# Interconnect_board_v1p5.net
KiCad netlist of a schematic drawn in EAGLE
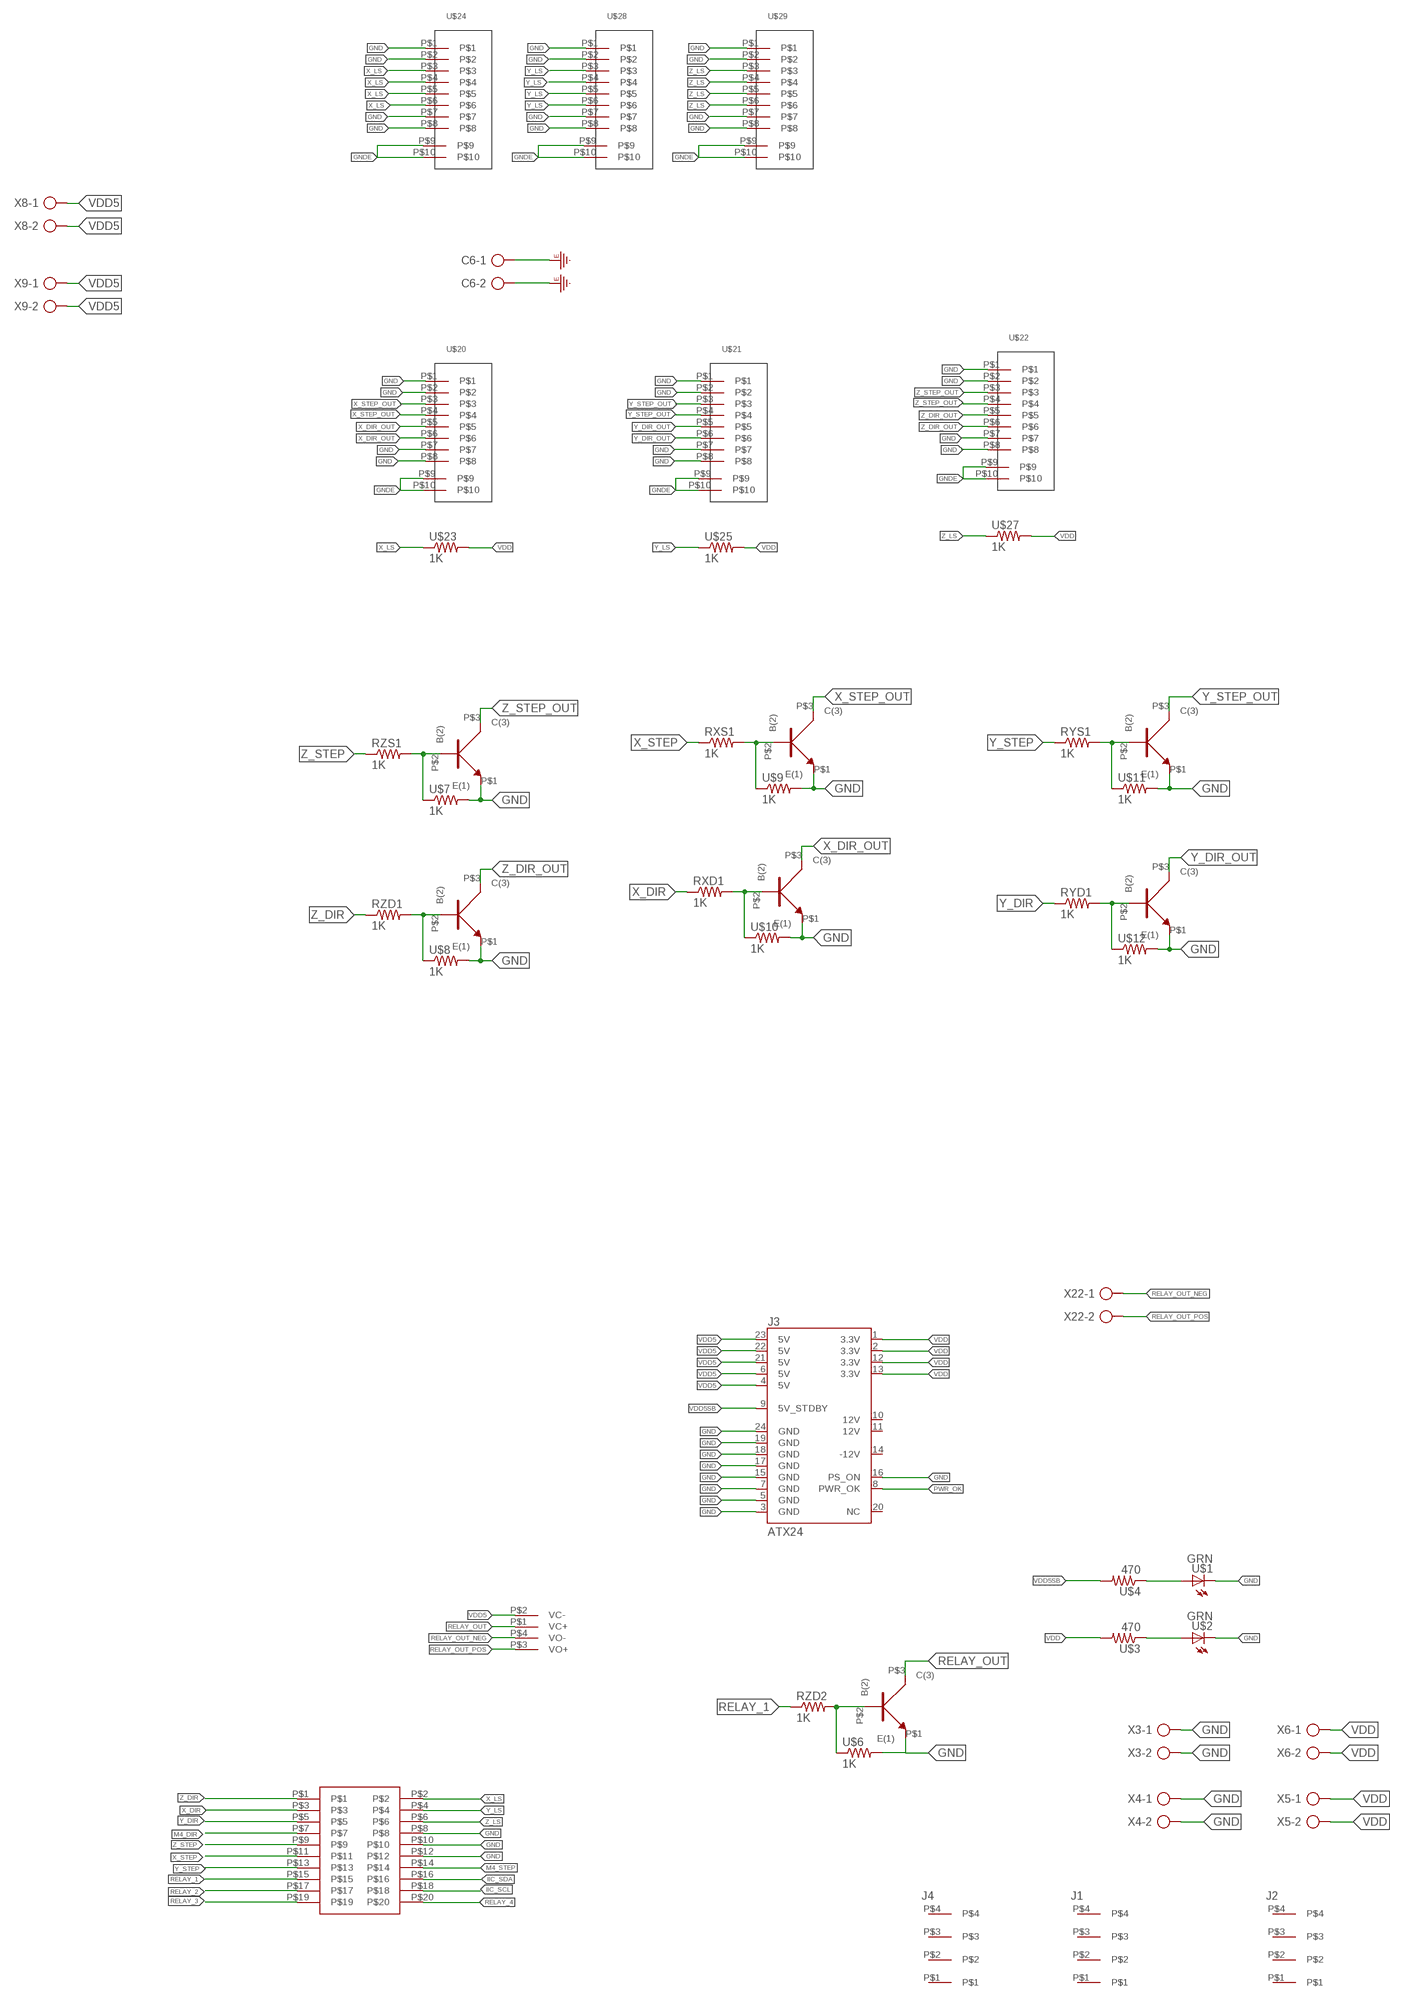
[diagram p0: schematic, sheet 1]

(export (version "E")
  (design (tool "Eeschema 10.0.6"))
  (components
    (comp (ref "C6")
      (value "AK300/2")
      (footprint "eagle-import:AK300_2")
      (libsource (lib "eagle-import") (part "AK300/2"))
    )
    (comp (ref "J1")
      (value "3.81MM_1_X_4_RT_ANGLE_PLUG_HEADER")
      (footprint "eagle-import:1X4_3.81MM_PITCH")
      (libsource (lib "eagle-import") (part "3.81MM_1_X_4_RT_ANGLE_PLUG_HEADER"))
    )
    (comp (ref "J2")
      (value "3.81MM_1_X_4_RT_ANGLE_PLUG_HEADER")
      (footprint "eagle-import:1X4_3.81MM_PITCH")
      (libsource (lib "eagle-import") (part "3.81MM_1_X_4_RT_ANGLE_PLUG_HEADER"))
    )
    (comp (ref "J3")
      (value "ATX24")
      (footprint "eagle-import:ATX24_STRAIGHT")
      (libsource (lib "eagle-import") (part "ATX24"))
    )
    (comp (ref "J4")
      (value "3.81MM_1_X_4_RT_ANGLE_PLUG_HEADER")
      (footprint "eagle-import:1X4_3.81MM_PITCH")
      (libsource (lib "eagle-import") (part "3.81MM_1_X_4_RT_ANGLE_PLUG_HEADER"))
    )
    (comp (ref "RXD1")
      (value "R_0805_1K")
      (footprint "eagle-import:R_0805_1K")
      (libsource (lib "eagle-import") (part "R_0805_1K"))
    )
    (comp (ref "RXS1")
      (value "R_0805_1K")
      (footprint "eagle-import:R_0805_1K")
      (libsource (lib "eagle-import") (part "R_0805_1K"))
    )
    (comp (ref "RYD1")
      (value "R_0805_1K")
      (footprint "eagle-import:R_0805_1K")
      (libsource (lib "eagle-import") (part "R_0805_1K"))
    )
    (comp (ref "RYS1")
      (value "R_0805_1K")
      (footprint "eagle-import:R_0805_1K")
      (libsource (lib "eagle-import") (part "R_0805_1K"))
    )
    (comp (ref "RZD1")
      (value "R_0805_1K")
      (footprint "eagle-import:R_0805_1K")
      (libsource (lib "eagle-import") (part "R_0805_1K"))
    )
    (comp (ref "RZD2")
      (value "R_0805_1K")
      (footprint "eagle-import:R_0805_1K")
      (libsource (lib "eagle-import") (part "R_0805_1K"))
    )
    (comp (ref "RZS1")
      (value "R_0805_1K")
      (footprint "eagle-import:R_0805_1K")
      (libsource (lib "eagle-import") (part "R_0805_1K"))
    )
    (comp (ref "U$1")
      (value "LED_0805_GREEN")
      (footprint "eagle-import:LED_0805_GREEN")
      (libsource (lib "eagle-import") (part "LED_0805_GREEN"))
    )
    (comp (ref "U$2")
      (value "LED_0805_GREEN")
      (footprint "eagle-import:LED_0805_GREEN")
      (libsource (lib "eagle-import") (part "LED_0805_GREEN"))
    )
    (comp (ref "U$3")
      (value "R_0805_470")
      (footprint "eagle-import:R_0805_470")
      (libsource (lib "eagle-import") (part "R_0805_470"))
    )
    (comp (ref "U$4")
      (value "R_0805_470")
      (footprint "eagle-import:R_0805_470")
      (libsource (lib "eagle-import") (part "R_0805_470"))
    )
    (comp (ref "U$5")
      (value "RELAY_KYOTO_KF0604D")
      (footprint "eagle-import:RELAY_KYOTO_KF0604D")
      (libsource (lib "eagle-import") (part "RELAY_KYOTO_KF0604D"))
    )
    (comp (ref "U$6")
      (value "R_0805_1K")
      (footprint "eagle-import:R_0805_1K")
      (libsource (lib "eagle-import") (part "R_0805_1K"))
    )
    (comp (ref "U$7")
      (value "R_0805_1K")
      (footprint "eagle-import:R_0805_1K")
      (libsource (lib "eagle-import") (part "R_0805_1K"))
    )
    (comp (ref "U$8")
      (value "R_0805_1K")
      (footprint "eagle-import:R_0805_1K")
      (libsource (lib "eagle-import") (part "R_0805_1K"))
    )
    (comp (ref "U$9")
      (value "R_0805_1K")
      (footprint "eagle-import:R_0805_1K")
      (libsource (lib "eagle-import") (part "R_0805_1K"))
    )
    (comp (ref "U$10")
      (value "R_0805_1K")
      (footprint "eagle-import:R_0805_1K")
      (libsource (lib "eagle-import") (part "R_0805_1K"))
    )
    (comp (ref "U$11")
      (value "R_0805_1K")
      (footprint "eagle-import:R_0805_1K")
      (libsource (lib "eagle-import") (part "R_0805_1K"))
    )
    (comp (ref "U$12")
      (value "R_0805_1K")
      (footprint "eagle-import:R_0805_1K")
      (libsource (lib "eagle-import") (part "R_0805_1K"))
    )
    (comp (ref "U$13")
      (value "TRANS_NPN")
      (footprint "eagle-import:TO_92_STRAIGHT")
      (libsource (lib "eagle-import") (part "TRANS_NPN"))
    )
    (comp (ref "U$14")
      (value "TRANS_NPN")
      (footprint "eagle-import:TO_92_STRAIGHT")
      (libsource (lib "eagle-import") (part "TRANS_NPN"))
    )
    (comp (ref "U$15")
      (value "TRANS_NPN")
      (footprint "eagle-import:TO_92_STRAIGHT")
      (libsource (lib "eagle-import") (part "TRANS_NPN"))
    )
    (comp (ref "U$16")
      (value "TRANS_NPN")
      (footprint "eagle-import:TO_92_STRAIGHT")
      (libsource (lib "eagle-import") (part "TRANS_NPN"))
    )
    (comp (ref "U$17")
      (value "TRANS_NPN")
      (footprint "eagle-import:TO_92_STRAIGHT")
      (libsource (lib "eagle-import") (part "TRANS_NPN"))
    )
    (comp (ref "U$18")
      (value "TRANS_NPN")
      (footprint "eagle-import:TO_92_STRAIGHT")
      (libsource (lib "eagle-import") (part "TRANS_NPN"))
    )
    (comp (ref "U$19")
      (value "TRANS_NPN")
      (footprint "eagle-import:TO_92_STRAIGHT")
      (libsource (lib "eagle-import") (part "TRANS_NPN"))
    )
    (comp (ref "U$20")
      (value "RJ45_SMTRJ")
      (footprint "eagle-import:RJ45_SMT")
      (libsource (lib "eagle-import") (part "RJ45_SMTRJ"))
    )
    (comp (ref "U$21")
      (value "RJ45_SMTRJ")
      (footprint "eagle-import:RJ45_SMT")
      (libsource (lib "eagle-import") (part "RJ45_SMTRJ"))
    )
    (comp (ref "U$22")
      (value "RJ45_SMTRJ")
      (footprint "eagle-import:RJ45_SMT")
      (libsource (lib "eagle-import") (part "RJ45_SMTRJ"))
    )
    (comp (ref "U$23")
      (value "R_0805_1K")
      (footprint "eagle-import:R_0805_1K")
      (libsource (lib "eagle-import") (part "R_0805_1K"))
    )
    (comp (ref "U$24")
      (value "RJ45_SMTRJ")
      (footprint "eagle-import:RJ45_SMT")
      (libsource (lib "eagle-import") (part "RJ45_SMTRJ"))
    )
    (comp (ref "U$25")
      (value "R_0805_1K")
      (footprint "eagle-import:R_0805_1K")
      (libsource (lib "eagle-import") (part "R_0805_1K"))
    )
    (comp (ref "U$26")
      (value "2_X_10_HEADER_GENERIC")
      (footprint "eagle-import:2_X_10_.1_INCH")
      (libsource (lib "eagle-import") (part "2_X_10_HEADER_GENERIC"))
    )
    (comp (ref "U$27")
      (value "R_0805_1K")
      (footprint "eagle-import:R_0805_1K")
      (libsource (lib "eagle-import") (part "R_0805_1K"))
    )
    (comp (ref "U$28")
      (value "RJ45_SMTRJ")
      (footprint "eagle-import:RJ45_SMT")
      (libsource (lib "eagle-import") (part "RJ45_SMTRJ"))
    )
    (comp (ref "U$29")
      (value "RJ45_SMTRJ")
      (footprint "eagle-import:RJ45_SMT")
      (libsource (lib "eagle-import") (part "RJ45_SMTRJ"))
    )
    (comp (ref "X3")
      (value "AK300/2")
      (footprint "eagle-import:AK300_2")
      (libsource (lib "eagle-import") (part "AK300/2"))
    )
    (comp (ref "X4")
      (value "AK300/2")
      (footprint "eagle-import:AK300_2")
      (libsource (lib "eagle-import") (part "AK300/2"))
    )
    (comp (ref "X5")
      (value "AK300/2")
      (footprint "eagle-import:AK300_2")
      (libsource (lib "eagle-import") (part "AK300/2"))
    )
    (comp (ref "X6")
      (value "AK300/2")
      (footprint "eagle-import:AK300_2")
      (libsource (lib "eagle-import") (part "AK300/2"))
    )
    (comp (ref "X8")
      (value "AK300/2")
      (footprint "eagle-import:AK300_2")
      (libsource (lib "eagle-import") (part "AK300/2"))
    )
    (comp (ref "X9")
      (value "AK300/2")
      (footprint "eagle-import:AK300_2")
      (libsource (lib "eagle-import") (part "AK300/2"))
    )
    (comp (ref "X22")
      (value "AK300/2")
      (footprint "eagle-import:AK300_2")
      (libsource (lib "eagle-import") (part "AK300/2"))
    )
  )
  (nets
    (net (code "1") (name "GND") (class "Default")
      (node (ref "J3") (pin "15") (pinfunction "GND_15") (pintype "bidirectional"))
      (node (ref "J3") (pin "16") (pinfunction "PS_ON_16") (pintype "bidirectional"))
      (node (ref "J3") (pin "17") (pinfunction "GND_17") (pintype "bidirectional"))
      (node (ref "J3") (pin "18") (pinfunction "GND_18") (pintype "bidirectional"))
      (node (ref "J3") (pin "19") (pinfunction "GND_19") (pintype "bidirectional"))
      (node (ref "J3") (pin "24") (pinfunction "GND_24") (pintype "bidirectional"))
      (node (ref "J3") (pin "3") (pinfunction "GND_3") (pintype "bidirectional"))
      (node (ref "J3") (pin "5") (pinfunction "GND_5") (pintype "bidirectional"))
      (node (ref "J3") (pin "7") (pinfunction "GND_7") (pintype "bidirectional"))
      (node (ref "U$1") (pin "C") (pinfunction "C_C") (pintype "passive"))
      (node (ref "U$10") (pin "2") (pinfunction "2_2") (pintype "passive"))
      (node (ref "U$11") (pin "2") (pinfunction "2_2") (pintype "passive"))
      (node (ref "U$12") (pin "2") (pinfunction "2_2") (pintype "passive"))
      (node (ref "U$13") (pin "P$1") (pinfunction "E(1)_P$1") (pintype "output"))
      (node (ref "U$14") (pin "P$1") (pinfunction "E(1)_P$1") (pintype "output"))
      (node (ref "U$15") (pin "P$1") (pinfunction "E(1)_P$1") (pintype "output"))
      (node (ref "U$16") (pin "P$1") (pinfunction "E(1)_P$1") (pintype "output"))
      (node (ref "U$17") (pin "P$1") (pinfunction "E(1)_P$1") (pintype "output"))
      (node (ref "U$18") (pin "P$1") (pinfunction "E(1)_P$1") (pintype "output"))
      (node (ref "U$19") (pin "P$1") (pinfunction "E(1)_P$1") (pintype "output"))
      (node (ref "U$2") (pin "C") (pinfunction "C_C") (pintype "passive"))
      (node (ref "U$20") (pin "P$1") (pinfunction "P$1_P$1") (pintype "bidirectional"))
      (node (ref "U$20") (pin "P$2") (pinfunction "P$2_P$2") (pintype "bidirectional"))
      (node (ref "U$20") (pin "P$7") (pinfunction "P$7_P$7") (pintype "bidirectional"))
      (node (ref "U$20") (pin "P$8") (pinfunction "P$8_P$8") (pintype "bidirectional"))
      (node (ref "U$21") (pin "P$1") (pinfunction "P$1_P$1") (pintype "bidirectional"))
      (node (ref "U$21") (pin "P$2") (pinfunction "P$2_P$2") (pintype "bidirectional"))
      (node (ref "U$21") (pin "P$7") (pinfunction "P$7_P$7") (pintype "bidirectional"))
      (node (ref "U$21") (pin "P$8") (pinfunction "P$8_P$8") (pintype "bidirectional"))
      (node (ref "U$22") (pin "P$1") (pinfunction "P$1_P$1") (pintype "bidirectional"))
      (node (ref "U$22") (pin "P$2") (pinfunction "P$2_P$2") (pintype "bidirectional"))
      (node (ref "U$22") (pin "P$7") (pinfunction "P$7_P$7") (pintype "bidirectional"))
      (node (ref "U$22") (pin "P$8") (pinfunction "P$8_P$8") (pintype "bidirectional"))
      (node (ref "U$24") (pin "P$1") (pinfunction "P$1_P$1") (pintype "bidirectional"))
      (node (ref "U$24") (pin "P$2") (pinfunction "P$2_P$2") (pintype "bidirectional"))
      (node (ref "U$24") (pin "P$7") (pinfunction "P$7_P$7") (pintype "bidirectional"))
      (node (ref "U$24") (pin "P$8") (pinfunction "P$8_P$8") (pintype "bidirectional"))
      (node (ref "U$26") (pin "P$10") (pinfunction "P$10_P$10") (pintype "bidirectional"))
      (node (ref "U$26") (pin "P$12") (pinfunction "P$12_P$12") (pintype "bidirectional"))
      (node (ref "U$26") (pin "P$8") (pinfunction "P$8_P$8") (pintype "bidirectional"))
      (node (ref "U$28") (pin "P$1") (pinfunction "P$1_P$1") (pintype "bidirectional"))
      (node (ref "U$28") (pin "P$2") (pinfunction "P$2_P$2") (pintype "bidirectional"))
      (node (ref "U$28") (pin "P$7") (pinfunction "P$7_P$7") (pintype "bidirectional"))
      (node (ref "U$28") (pin "P$8") (pinfunction "P$8_P$8") (pintype "bidirectional"))
      (node (ref "U$29") (pin "P$1") (pinfunction "P$1_P$1") (pintype "bidirectional"))
      (node (ref "U$29") (pin "P$2") (pinfunction "P$2_P$2") (pintype "bidirectional"))
      (node (ref "U$29") (pin "P$7") (pinfunction "P$7_P$7") (pintype "bidirectional"))
      (node (ref "U$29") (pin "P$8") (pinfunction "P$8_P$8") (pintype "bidirectional"))
      (node (ref "U$6") (pin "2") (pinfunction "2_2") (pintype "passive"))
      (node (ref "U$7") (pin "2") (pinfunction "2_2") (pintype "passive"))
      (node (ref "U$8") (pin "2") (pinfunction "2_2") (pintype "passive"))
      (node (ref "U$9") (pin "2") (pinfunction "2_2") (pintype "passive"))
      (node (ref "X3") (pin "1") (pinfunction "KL_1") (pintype "passive"))
      (node (ref "X3") (pin "2") (pinfunction "KL_2") (pintype "passive"))
      (node (ref "X4") (pin "1") (pinfunction "KL_1") (pintype "passive"))
      (node (ref "X4") (pin "2") (pinfunction "KL_2") (pintype "passive"))
    )
    (net (code "2") (name "GNDE") (class "Default")
      (node (ref "C6") (pin "1") (pinfunction "KL_1") (pintype "passive"))
      (node (ref "C6") (pin "2") (pinfunction "KL_2") (pintype "passive"))
      (node (ref "U$20") (pin "P$10") (pinfunction "P$10_P$10") (pintype "bidirectional"))
      (node (ref "U$20") (pin "P$9") (pinfunction "P$9_P$9") (pintype "bidirectional"))
      (node (ref "U$21") (pin "P$10") (pinfunction "P$10_P$10") (pintype "bidirectional"))
      (node (ref "U$21") (pin "P$9") (pinfunction "P$9_P$9") (pintype "bidirectional"))
      (node (ref "U$22") (pin "P$10") (pinfunction "P$10_P$10") (pintype "bidirectional"))
      (node (ref "U$22") (pin "P$9") (pinfunction "P$9_P$9") (pintype "bidirectional"))
      (node (ref "U$24") (pin "P$10") (pinfunction "P$10_P$10") (pintype "bidirectional"))
      (node (ref "U$24") (pin "P$9") (pinfunction "P$9_P$9") (pintype "bidirectional"))
      (node (ref "U$28") (pin "P$10") (pinfunction "P$10_P$10") (pintype "bidirectional"))
      (node (ref "U$28") (pin "P$9") (pinfunction "P$9_P$9") (pintype "bidirectional"))
      (node (ref "U$29") (pin "P$10") (pinfunction "P$10_P$10") (pintype "bidirectional"))
      (node (ref "U$29") (pin "P$9") (pinfunction "P$9_P$9") (pintype "bidirectional"))
    )
    (net (code "3") (name "IIC_SCL") (class "Default")
      (node (ref "U$26") (pin "P$18") (pinfunction "P$18_P$18") (pintype "bidirectional"))
    )
    (net (code "4") (name "IIC_SDA") (class "Default")
      (node (ref "U$26") (pin "P$16") (pinfunction "P$16_P$16") (pintype "bidirectional"))
    )
    (net (code "5") (name "M4_DIR") (class "Default")
      (node (ref "U$26") (pin "P$7") (pinfunction "P$7_P$7") (pintype "bidirectional"))
    )
    (net (code "6") (name "M4_STEP") (class "Default")
      (node (ref "U$26") (pin "P$14") (pinfunction "P$14_P$14") (pintype "bidirectional"))
    )
    (net (code "7") (name "Net-(U$1-PadA)") (class "Default")
      (node (ref "U$1") (pin "A") (pinfunction "A_A") (pintype "passive"))
      (node (ref "U$4") (pin "1") (pinfunction "1_1") (pintype "passive"))
    )
    (net (code "8") (name "Net-(U$2-PadA)") (class "Default")
      (node (ref "U$2") (pin "A") (pinfunction "A_A") (pintype "passive"))
      (node (ref "U$3") (pin "1") (pinfunction "1_1") (pintype "passive"))
    )
    (net (code "9") (name "Net-(U$13-B(2))") (class "Default")
      (node (ref "RZS1") (pin "2") (pinfunction "2_2") (pintype "passive"))
      (node (ref "U$13") (pin "P$2") (pinfunction "B(2)_P$2") (pintype "input"))
      (node (ref "U$7") (pin "1") (pinfunction "1_1") (pintype "passive"))
    )
    (net (code "10") (name "Net-(U$14-B(2))") (class "Default")
      (node (ref "RZD1") (pin "2") (pinfunction "2_2") (pintype "passive"))
      (node (ref "U$14") (pin "P$2") (pinfunction "B(2)_P$2") (pintype "input"))
      (node (ref "U$8") (pin "1") (pinfunction "1_1") (pintype "passive"))
    )
    (net (code "11") (name "Net-(U$15-B(2))") (class "Default")
      (node (ref "RXS1") (pin "2") (pinfunction "2_2") (pintype "passive"))
      (node (ref "U$15") (pin "P$2") (pinfunction "B(2)_P$2") (pintype "input"))
      (node (ref "U$9") (pin "1") (pinfunction "1_1") (pintype "passive"))
    )
    (net (code "12") (name "Net-(U$16-B(2))") (class "Default")
      (node (ref "RXD1") (pin "2") (pinfunction "2_2") (pintype "passive"))
      (node (ref "U$10") (pin "1") (pinfunction "1_1") (pintype "passive"))
      (node (ref "U$16") (pin "P$2") (pinfunction "B(2)_P$2") (pintype "input"))
    )
    (net (code "13") (name "Net-(U$17-B(2))") (class "Default")
      (node (ref "RYD1") (pin "2") (pinfunction "2_2") (pintype "passive"))
      (node (ref "U$12") (pin "1") (pinfunction "1_1") (pintype "passive"))
      (node (ref "U$17") (pin "P$2") (pinfunction "B(2)_P$2") (pintype "input"))
    )
    (net (code "14") (name "Net-(U$18-B(2))") (class "Default")
      (node (ref "RYS1") (pin "2") (pinfunction "2_2") (pintype "passive"))
      (node (ref "U$11") (pin "1") (pinfunction "1_1") (pintype "passive"))
      (node (ref "U$18") (pin "P$2") (pinfunction "B(2)_P$2") (pintype "input"))
    )
    (net (code "15") (name "Net-(U$19-B(2))") (class "Default")
      (node (ref "RZD2") (pin "2") (pinfunction "2_2") (pintype "passive"))
      (node (ref "U$19") (pin "P$2") (pinfunction "B(2)_P$2") (pintype "input"))
      (node (ref "U$6") (pin "1") (pinfunction "1_1") (pintype "passive"))
    )
    (net (code "16") (name "PWR_OK") (class "Default")
      (node (ref "J3") (pin "8") (pinfunction "PWR_OK_8") (pintype "bidirectional"))
    )
    (net (code "17") (name "RELAY_1") (class "Default")
      (node (ref "RZD2") (pin "1") (pinfunction "1_1") (pintype "passive"))
      (node (ref "U$26") (pin "P$15") (pinfunction "P$15_P$15") (pintype "bidirectional"))
    )
    (net (code "18") (name "RELAY_2") (class "Default")
      (node (ref "U$26") (pin "P$17") (pinfunction "P$17_P$17") (pintype "bidirectional"))
    )
    (net (code "19") (name "RELAY_3") (class "Default")
      (node (ref "U$26") (pin "P$19") (pinfunction "P$19_P$19") (pintype "bidirectional"))
    )
    (net (code "20") (name "RELAY_4") (class "Default")
      (node (ref "U$26") (pin "P$20") (pinfunction "P$20_P$20") (pintype "bidirectional"))
    )
    (net (code "21") (name "RELAY_OUT") (class "Default")
      (node (ref "U$19") (pin "P$3") (pinfunction "C(3)_P$3") (pintype "input"))
      (node (ref "U$5") (pin "P$1") (pinfunction "VC+_P$1") (pintype "bidirectional"))
    )
    (net (code "22") (name "RELAY_OUT_NEG") (class "Default")
      (node (ref "U$5") (pin "P$4") (pinfunction "VO-_P$4") (pintype "bidirectional"))
      (node (ref "X22") (pin "1") (pinfunction "KL_1") (pintype "passive"))
    )
    (net (code "23") (name "RELAY_OUT_POS") (class "Default")
      (node (ref "U$5") (pin "P$3") (pinfunction "VO+_P$3") (pintype "bidirectional"))
      (node (ref "X22") (pin "2") (pinfunction "KL_2") (pintype "passive"))
    )
    (net (code "24") (name "VDD") (class "Default")
      (node (ref "J3") (pin "1") (pinfunction "3.3V_1") (pintype "bidirectional"))
      (node (ref "J3") (pin "12") (pinfunction "3.3V_12") (pintype "bidirectional"))
      (node (ref "J3") (pin "13") (pinfunction "3.3V_13") (pintype "bidirectional"))
      (node (ref "J3") (pin "2") (pinfunction "3.3V_2") (pintype "bidirectional"))
      (node (ref "U$23") (pin "2") (pinfunction "2_2") (pintype "passive"))
      (node (ref "U$25") (pin "2") (pinfunction "2_2") (pintype "passive"))
      (node (ref "U$27") (pin "2") (pinfunction "2_2") (pintype "passive"))
      (node (ref "U$3") (pin "2") (pinfunction "2_2") (pintype "passive"))
      (node (ref "X5") (pin "1") (pinfunction "KL_1") (pintype "passive"))
      (node (ref "X5") (pin "2") (pinfunction "KL_2") (pintype "passive"))
      (node (ref "X6") (pin "1") (pinfunction "KL_1") (pintype "passive"))
      (node (ref "X6") (pin "2") (pinfunction "KL_2") (pintype "passive"))
    )
    (net (code "25") (name "VDD5") (class "Default")
      (node (ref "J3") (pin "21") (pinfunction "5V_21") (pintype "bidirectional"))
      (node (ref "J3") (pin "22") (pinfunction "5V_22") (pintype "bidirectional"))
      (node (ref "J3") (pin "23") (pinfunction "5V_23") (pintype "bidirectional"))
      (node (ref "J3") (pin "4") (pinfunction "5V_4") (pintype "bidirectional"))
      (node (ref "J3") (pin "6") (pinfunction "5V_6") (pintype "bidirectional"))
      (node (ref "U$5") (pin "P$2") (pinfunction "VC-_P$2") (pintype "bidirectional"))
      (node (ref "X8") (pin "1") (pinfunction "KL_1") (pintype "passive"))
      (node (ref "X8") (pin "2") (pinfunction "KL_2") (pintype "passive"))
      (node (ref "X9") (pin "1") (pinfunction "KL_1") (pintype "passive"))
      (node (ref "X9") (pin "2") (pinfunction "KL_2") (pintype "passive"))
    )
    (net (code "26") (name "VDD5SB") (class "Default")
      (node (ref "J3") (pin "9") (pinfunction "5V_STDBY_9") (pintype "bidirectional"))
      (node (ref "U$4") (pin "2") (pinfunction "2_2") (pintype "passive"))
    )
    (net (code "27") (name "X_DIR") (class "Default")
      (node (ref "RXD1") (pin "1") (pinfunction "1_1") (pintype "passive"))
      (node (ref "U$26") (pin "P$3") (pinfunction "P$3_P$3") (pintype "bidirectional"))
    )
    (net (code "28") (name "X_DIR_OUT") (class "Default")
      (node (ref "U$16") (pin "P$3") (pinfunction "C(3)_P$3") (pintype "input"))
      (node (ref "U$20") (pin "P$5") (pinfunction "P$5_P$5") (pintype "bidirectional"))
      (node (ref "U$20") (pin "P$6") (pinfunction "P$6_P$6") (pintype "bidirectional"))
    )
    (net (code "29") (name "X_LS") (class "Default")
      (node (ref "U$23") (pin "1") (pinfunction "1_1") (pintype "passive"))
      (node (ref "U$24") (pin "P$3") (pinfunction "P$3_P$3") (pintype "bidirectional"))
      (node (ref "U$24") (pin "P$4") (pinfunction "P$4_P$4") (pintype "bidirectional"))
      (node (ref "U$24") (pin "P$5") (pinfunction "P$5_P$5") (pintype "bidirectional"))
      (node (ref "U$24") (pin "P$6") (pinfunction "P$6_P$6") (pintype "bidirectional"))
      (node (ref "U$26") (pin "P$2") (pinfunction "P$2_P$2") (pintype "bidirectional"))
    )
    (net (code "30") (name "X_STEP") (class "Default")
      (node (ref "RXS1") (pin "1") (pinfunction "1_1") (pintype "passive"))
      (node (ref "U$26") (pin "P$11") (pinfunction "P$11_P$11") (pintype "bidirectional"))
    )
    (net (code "31") (name "X_STEP_OUT") (class "Default")
      (node (ref "U$15") (pin "P$3") (pinfunction "C(3)_P$3") (pintype "input"))
      (node (ref "U$20") (pin "P$3") (pinfunction "P$3_P$3") (pintype "bidirectional"))
      (node (ref "U$20") (pin "P$4") (pinfunction "P$4_P$4") (pintype "bidirectional"))
    )
    (net (code "32") (name "Y_DIR") (class "Default")
      (node (ref "RYD1") (pin "1") (pinfunction "1_1") (pintype "passive"))
      (node (ref "U$26") (pin "P$5") (pinfunction "P$5_P$5") (pintype "bidirectional"))
    )
    (net (code "33") (name "Y_DIR_OUT") (class "Default")
      (node (ref "U$17") (pin "P$3") (pinfunction "C(3)_P$3") (pintype "input"))
      (node (ref "U$21") (pin "P$5") (pinfunction "P$5_P$5") (pintype "bidirectional"))
      (node (ref "U$21") (pin "P$6") (pinfunction "P$6_P$6") (pintype "bidirectional"))
    )
    (net (code "34") (name "Y_LS") (class "Default")
      (node (ref "U$25") (pin "1") (pinfunction "1_1") (pintype "passive"))
      (node (ref "U$26") (pin "P$4") (pinfunction "P$4_P$4") (pintype "bidirectional"))
      (node (ref "U$28") (pin "P$3") (pinfunction "P$3_P$3") (pintype "bidirectional"))
      (node (ref "U$28") (pin "P$4") (pinfunction "P$4_P$4") (pintype "bidirectional"))
      (node (ref "U$28") (pin "P$5") (pinfunction "P$5_P$5") (pintype "bidirectional"))
      (node (ref "U$28") (pin "P$6") (pinfunction "P$6_P$6") (pintype "bidirectional"))
    )
    (net (code "35") (name "Y_STEP") (class "Default")
      (node (ref "RYS1") (pin "1") (pinfunction "1_1") (pintype "passive"))
      (node (ref "U$26") (pin "P$13") (pinfunction "P$13_P$13") (pintype "bidirectional"))
    )
    (net (code "36") (name "Y_STEP_OUT") (class "Default")
      (node (ref "U$18") (pin "P$3") (pinfunction "C(3)_P$3") (pintype "input"))
      (node (ref "U$21") (pin "P$3") (pinfunction "P$3_P$3") (pintype "bidirectional"))
      (node (ref "U$21") (pin "P$4") (pinfunction "P$4_P$4") (pintype "bidirectional"))
    )
    (net (code "37") (name "Z_DIR") (class "Default")
      (node (ref "RZD1") (pin "1") (pinfunction "1_1") (pintype "passive"))
      (node (ref "U$26") (pin "P$1") (pinfunction "P$1_P$1") (pintype "bidirectional"))
    )
    (net (code "38") (name "Z_DIR_OUT") (class "Default")
      (node (ref "U$14") (pin "P$3") (pinfunction "C(3)_P$3") (pintype "input"))
      (node (ref "U$22") (pin "P$5") (pinfunction "P$5_P$5") (pintype "bidirectional"))
      (node (ref "U$22") (pin "P$6") (pinfunction "P$6_P$6") (pintype "bidirectional"))
    )
    (net (code "39") (name "Z_LS") (class "Default")
      (node (ref "U$26") (pin "P$6") (pinfunction "P$6_P$6") (pintype "bidirectional"))
      (node (ref "U$27") (pin "1") (pinfunction "1_1") (pintype "passive"))
      (node (ref "U$29") (pin "P$3") (pinfunction "P$3_P$3") (pintype "bidirectional"))
      (node (ref "U$29") (pin "P$4") (pinfunction "P$4_P$4") (pintype "bidirectional"))
      (node (ref "U$29") (pin "P$5") (pinfunction "P$5_P$5") (pintype "bidirectional"))
      (node (ref "U$29") (pin "P$6") (pinfunction "P$6_P$6") (pintype "bidirectional"))
    )
    (net (code "40") (name "Z_STEP") (class "Default")
      (node (ref "RZS1") (pin "1") (pinfunction "1_1") (pintype "passive"))
      (node (ref "U$26") (pin "P$9") (pinfunction "P$9_P$9") (pintype "bidirectional"))
    )
    (net (code "41") (name "Z_STEP_OUT") (class "Default")
      (node (ref "U$13") (pin "P$3") (pinfunction "C(3)_P$3") (pintype "input"))
      (node (ref "U$22") (pin "P$3") (pinfunction "P$3_P$3") (pintype "bidirectional"))
      (node (ref "U$22") (pin "P$4") (pinfunction "P$4_P$4") (pintype "bidirectional"))
    )
    (net (code "42") (name "unconnected-(J1-PadP$1)") (class "Default")
      (node (ref "J1") (pin "P$1") (pinfunction "P$1_P$1") (pintype "bidirectional"))
    )
    (net (code "43") (name "unconnected-(J1-PadP$2)") (class "Default")
      (node (ref "J1") (pin "P$2") (pinfunction "P$2_P$2") (pintype "bidirectional"))
    )
    (net (code "44") (name "unconnected-(J1-PadP$3)") (class "Default")
      (node (ref "J1") (pin "P$3") (pinfunction "P$3_P$3") (pintype "bidirectional"))
    )
    (net (code "45") (name "unconnected-(J1-PadP$4)") (class "Default")
      (node (ref "J1") (pin "P$4") (pinfunction "P$4_P$4") (pintype "bidirectional"))
    )
    (net (code "46") (name "unconnected-(J2-PadP$1)") (class "Default")
      (node (ref "J2") (pin "P$1") (pinfunction "P$1_P$1") (pintype "bidirectional"))
    )
    (net (code "47") (name "unconnected-(J2-PadP$2)") (class "Default")
      (node (ref "J2") (pin "P$2") (pinfunction "P$2_P$2") (pintype "bidirectional"))
    )
    (net (code "48") (name "unconnected-(J2-PadP$3)") (class "Default")
      (node (ref "J2") (pin "P$3") (pinfunction "P$3_P$3") (pintype "bidirectional"))
    )
    (net (code "49") (name "unconnected-(J2-PadP$4)") (class "Default")
      (node (ref "J2") (pin "P$4") (pinfunction "P$4_P$4") (pintype "bidirectional"))
    )
    (net (code "50") (name "unconnected-(J3--12V-Pad14)") (class "Default")
      (node (ref "J3") (pin "14") (pinfunction "-12V_14") (pintype "bidirectional"))
    )
    (net (code "51") (name "unconnected-(J3-12V-Pad10)") (class "Default")
      (node (ref "J3") (pin "10") (pinfunction "12V_10") (pintype "bidirectional"))
    )
    (net (code "52") (name "unconnected-(J3-12V-Pad11)") (class "Default")
      (node (ref "J3") (pin "11") (pinfunction "12V_11") (pintype "bidirectional"))
    )
    (net (code "53") (name "unconnected-(J3-NC-Pad20)") (class "Default")
      (node (ref "J3") (pin "20") (pinfunction "NC_20") (pintype "bidirectional"))
    )
    (net (code "54") (name "unconnected-(J4-PadP$1)") (class "Default")
      (node (ref "J4") (pin "P$1") (pinfunction "P$1_P$1") (pintype "bidirectional"))
    )
    (net (code "55") (name "unconnected-(J4-PadP$2)") (class "Default")
      (node (ref "J4") (pin "P$2") (pinfunction "P$2_P$2") (pintype "bidirectional"))
    )
    (net (code "56") (name "unconnected-(J4-PadP$3)") (class "Default")
      (node (ref "J4") (pin "P$3") (pinfunction "P$3_P$3") (pintype "bidirectional"))
    )
    (net (code "57") (name "unconnected-(J4-PadP$4)") (class "Default")
      (node (ref "J4") (pin "P$4") (pinfunction "P$4_P$4") (pintype "bidirectional"))
    )
  )
)
